# Current-LoadSwitches_3V3.net
KiCad netlist of a schematic drawn in Altium Designer
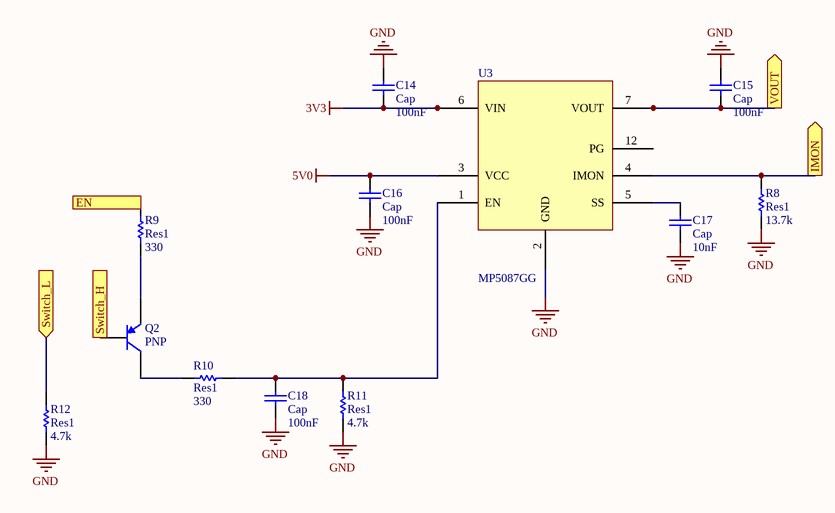
[diagram p0: Current-LoadSwitches 3V3.SchDoc]

(export (version "E")
  (design (tool "Eeschema 10.0.6"))
  (components
    (comp (ref "C14")
      (value "Cap")
      (footprint "0402-A")
      (description "Capacitor")
      (fields (field (name "ALTIUM_VALUE") "100nF") (field (name "PUBLISHER") "Altium Limited"))
      (libsource (lib "Miscellaneous Devices") (part "Cap"))
    )
    (comp (ref "C15")
      (value "Cap")
      (footprint "0402-A")
      (description "Capacitor")
      (fields (field (name "ALTIUM_VALUE") "100nF") (field (name "PUBLISHER") "Altium Limited"))
      (libsource (lib "Miscellaneous Devices") (part "Cap"))
    )
    (comp (ref "C16")
      (value "Cap")
      (footprint "0402-A")
      (description "Capacitor")
      (fields (field (name "ALTIUM_VALUE") "100nF") (field (name "PUBLISHER") "Altium Limited"))
      (libsource (lib "Miscellaneous Devices") (part "Cap"))
    )
    (comp (ref "C17")
      (value "Cap")
      (footprint "0402-A")
      (description "Capacitor")
      (fields (field (name "ALTIUM_VALUE") "10nF") (field (name "PUBLISHER") "Altium Limited"))
      (libsource (lib "Miscellaneous Devices") (part "Cap"))
    )
    (comp (ref "C18")
      (value "Cap")
      (footprint "0402-A")
      (description "Capacitor")
      (fields (field (name "ALTIUM_VALUE") "100nF") (field (name "PUBLISHER") "Altium Limited"))
      (libsource (lib "Miscellaneous Devices") (part "Cap"))
    )
    (comp (ref "Q2")
      (value "PNP")
      (footprint "SOT-23B_N")
      (description "PNP Bipolar Transistor")
      (fields (field (name "PUBLISHER") "Altium Limited"))
      (libsource (lib "Miscellaneous Devices") (part "PNP"))
    )
    (comp (ref "R8")
      (value "Res1")
      (footprint "0402-A")
      (description "Resistor")
      (fields (field (name "ALTIUM_VALUE") "13.7k") (field (name "PUBLISHER") "Altium Limited"))
      (libsource (lib "Miscellaneous Devices") (part "Res1"))
    )
    (comp (ref "R9")
      (value "Res1")
      (footprint "0402-A")
      (description "Resistor")
      (fields (field (name "ALTIUM_VALUE") "330") (field (name "PUBLISHER") "Altium Limited"))
      (libsource (lib "Miscellaneous Devices") (part "Res1"))
    )
    (comp (ref "R10")
      (value "Res1")
      (footprint "0402-A")
      (description "Resistor")
      (fields (field (name "ALTIUM_VALUE") "330") (field (name "PUBLISHER") "Altium Limited"))
      (libsource (lib "Miscellaneous Devices") (part "Res1"))
    )
    (comp (ref "R11")
      (value "Res1")
      (footprint "0402-A")
      (description "Resistor")
      (fields (field (name "ALTIUM_VALUE") "4.7k") (field (name "PUBLISHER") "Altium Limited"))
      (libsource (lib "Miscellaneous Devices") (part "Res1"))
    )
    (comp (ref "R12")
      (value "Res1")
      (footprint "0402-A")
      (description "Resistor")
      (fields (field (name "ALTIUM_VALUE") "4.7k") (field (name "PUBLISHER") "Altium Limited"))
      (libsource (lib "Miscellaneous Devices") (part "Res1"))
    )
    (comp (ref "U3")
      (value "MP5087GG")
      (footprint "MP5087GG-Z")
      (libsource (lib "MP5087GG-Z") (part "Component_1"))
    )
  )
  (nets
    (net (code "1") (name "/EN") (class "Default")
      (node (ref "R9") (pin "2") (pinfunction "2_2") (pintype "passive"))
    )
    (net (code "2") (name "/IMON") (class "Default")
      (node (ref "R8") (pin "2") (pinfunction "2_2") (pintype "passive"))
      (node (ref "U3") (pin "4") (pinfunction "IMON_4") (pintype "passive"))
    )
    (net (code "3") (name "/Switch_H") (class "Default")
      (node (ref "Q2") (pin "2") (pinfunction "B_2") (pintype "passive"))
    )
    (net (code "4") (name "/Switch_L") (class "Default")
      (node (ref "R12") (pin "2") (pinfunction "2_2") (pintype "passive"))
    )
    (net (code "5") (name "/VOUT") (class "Default")
      (node (ref "C15") (pin "1") (pinfunction "1_1") (pintype "passive"))
      (node (ref "U3") (pin "10") (pinfunction "VOUT_10") (pintype "passive"))
      (node (ref "U3") (pin "7") (pinfunction "VOUT_7") (pintype "passive"))
      (node (ref "U3") (pin "8") (pinfunction "VOUT_8") (pintype "passive"))
      (node (ref "U3") (pin "9") (pinfunction "VOUT_9") (pintype "passive"))
    )
    (net (code "6") (name "3V3") (class "Default")
      (node (ref "C14") (pin "1") (pinfunction "1_1") (pintype "passive"))
      (node (ref "U3") (pin "11") (pinfunction "VOUT_11") (pintype "passive"))
      (node (ref "U3") (pin "6") (pinfunction "VIN_6") (pintype "passive"))
    )
    (net (code "7") (name "5V0") (class "Default")
      (node (ref "C16") (pin "2") (pinfunction "2_2") (pintype "passive"))
      (node (ref "U3") (pin "3") (pinfunction "VCC_3") (pintype "passive"))
    )
    (net (code "8") (name "GND") (class "Default")
      (node (ref "C14") (pin "2") (pinfunction "2_2") (pintype "passive"))
      (node (ref "C15") (pin "2") (pinfunction "2_2") (pintype "passive"))
      (node (ref "C16") (pin "1") (pinfunction "1_1") (pintype "passive"))
      (node (ref "C17") (pin "1") (pinfunction "1_1") (pintype "passive"))
      (node (ref "C18") (pin "1") (pinfunction "1_1") (pintype "passive"))
      (node (ref "R11") (pin "1") (pinfunction "1_1") (pintype "passive"))
      (node (ref "R12") (pin "1") (pinfunction "1_1") (pintype "passive"))
      (node (ref "R8") (pin "1") (pinfunction "1_1") (pintype "passive"))
      (node (ref "U3") (pin "2") (pinfunction "GND_2") (pintype "passive"))
    )
    (net (code "9") (name "Net-(Q2-C)") (class "Default")
      (node (ref "Q2") (pin "1") (pinfunction "C_1") (pintype "passive"))
      (node (ref "R10") (pin "1") (pinfunction "1_1") (pintype "passive"))
    )
    (net (code "10") (name "Net-(Q2-E)") (class "Default")
      (node (ref "Q2") (pin "3") (pinfunction "E_3") (pintype "passive"))
      (node (ref "R9") (pin "1") (pinfunction "1_1") (pintype "passive"))
    )
    (net (code "11") (name "Net-(U3-EN)") (class "Default")
      (node (ref "C18") (pin "2") (pinfunction "2_2") (pintype "passive"))
      (node (ref "R10") (pin "2") (pinfunction "2_2") (pintype "passive"))
      (node (ref "R11") (pin "2") (pinfunction "2_2") (pintype "passive"))
      (node (ref "U3") (pin "1") (pinfunction "EN_1") (pintype "passive"))
    )
    (net (code "12") (name "Net-(U3-SS)") (class "Default")
      (node (ref "C17") (pin "2") (pinfunction "2_2") (pintype "passive"))
      (node (ref "U3") (pin "5") (pinfunction "SS_5") (pintype "passive"))
    )
    (net (code "13") (name "unconnected-(U3-PG-Pad12)") (class "Default")
      (node (ref "U3") (pin "12") (pinfunction "PG_12") (pintype "passive"))
    )
  )
)
